# ProDoc_XIAOntegratedV2_2025-09-06.net
KiCad netlist of a schematic drawn in EasyEDA Pro
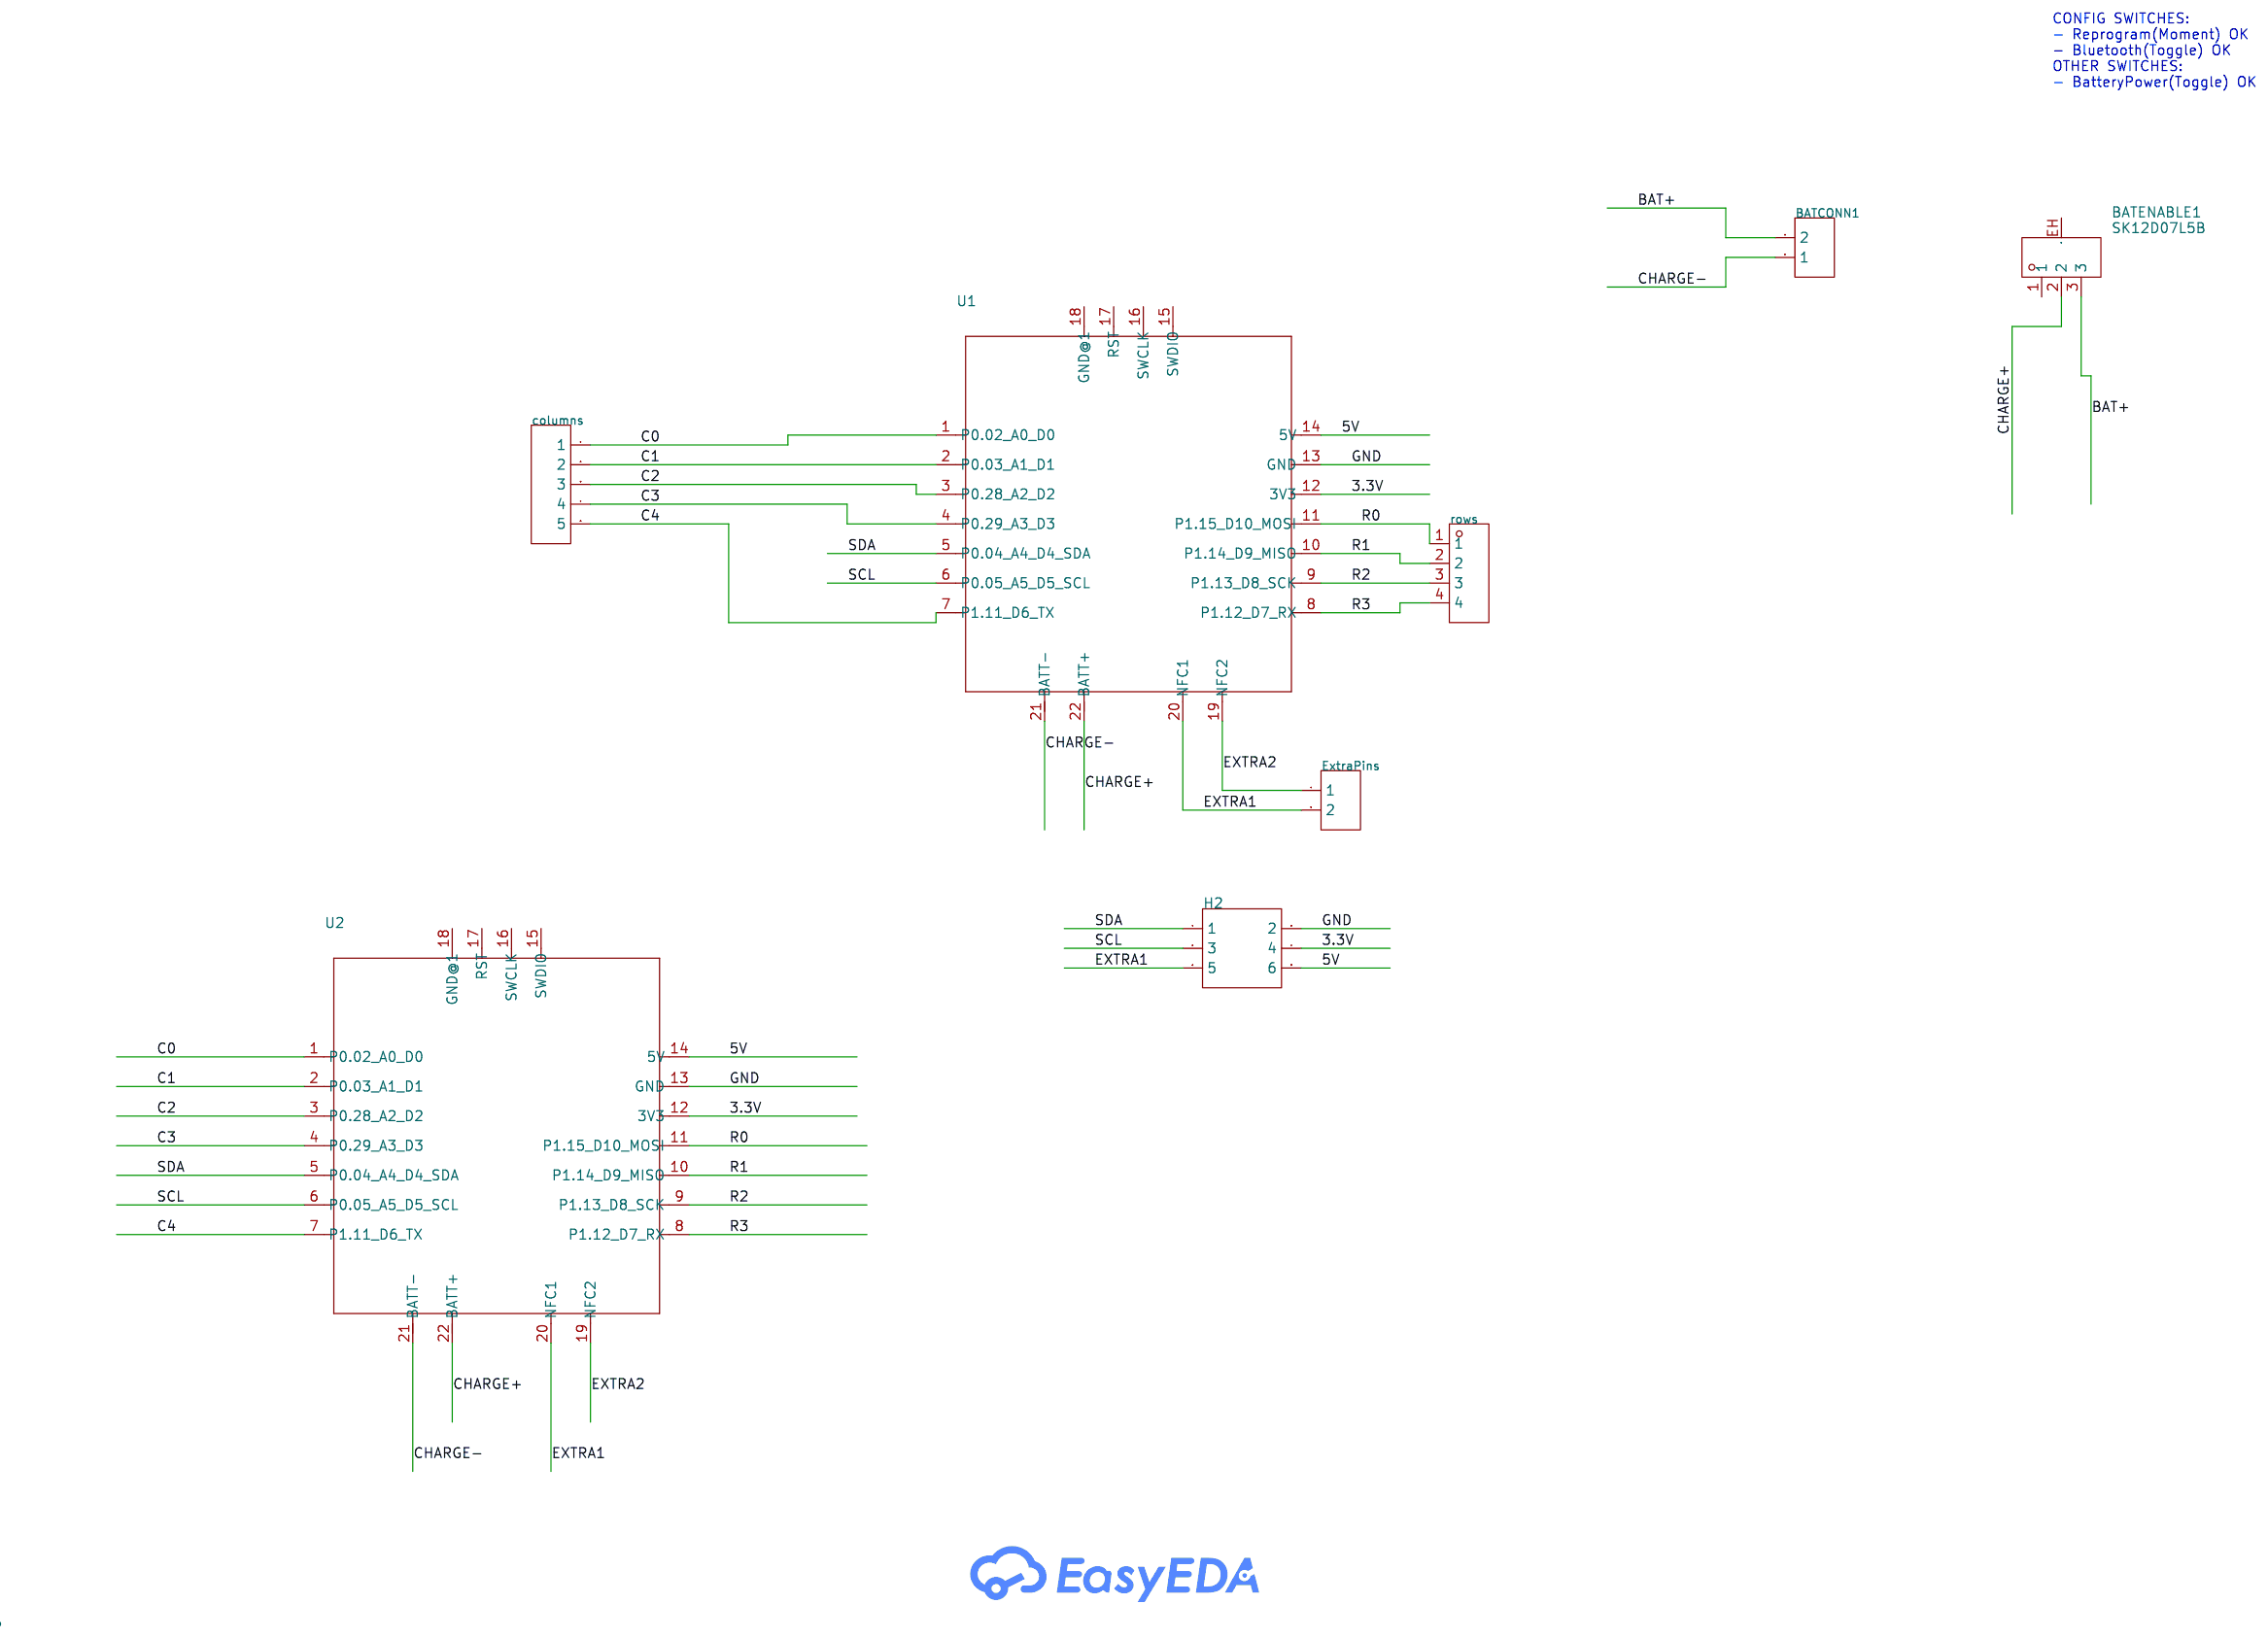
[diagram p0: schematic sheet]

(export (version "E")
  (design (tool "Eeschema 10.0.6"))
  (components
    (comp (ref "BATCONN1")
      (value "~")
      (footprint "easyedapro:HDR-TH_2P-P2.54-V-F")
      (libsource (lib "easyedapro") (part "Header-Female-2.54_1x2"))
    )
    (comp (ref "BATENABLE1")
      (value "SK12D07L5B")
      (footprint "easyedapro:SW-TH_SK-12D07-X-X")
      (fields (field (name "Manufacturer") "XKB Connection(中国星坤)"))
      (libsource (lib "easyedapro") (part "SK-12D07-L5-B"))
    )
    (comp (ref "columns")
      (value "~")
      (footprint "easyedapro:HDR-TH_5P-P2.54-V-F")
      (libsource (lib "easyedapro") (part "Header-Female-2.54_1x5"))
    )
    (comp (ref "ExtraPins")
      (value "~")
      (footprint "easyedapro:HDR-TH_2P-P2.54-V-F")
      (libsource (lib "easyedapro") (part "Header-Female-2.54_1x2"))
    )
    (comp (ref "H2")
      (value "~")
      (footprint "easyedapro:HDR-TH_6P-P2.54-V-F-R2-C3-S2.54")
      (libsource (lib "easyedapro") (part "HDR-F-2.54_2x3"))
    )
    (comp (ref "rows")
      (value "~")
      (footprint "easyedapro:HDR-TH_4P-P2.54-V-F")
      (libsource (lib "easyedapro") (part "2.54-1*4P母"))
    )
    (comp (ref "U1")
      (value "~")
      (footprint "easyedapro:XIAO-NRF52840/SENSE-MODULE14P-2.54-21X17.8MM")
      (libsource (lib "easyedapro") (part "XIAO-NRF52840/SENSE_"))
    )
    (comp (ref "U2")
      (value "~")
      (footprint "easyedapro:XIAO-NRF52840/SENSE-MODULE14P-2.54-21X17.8MM")
      (libsource (lib "easyedapro") (part "XIAO-NRF52840/SENSE_"))
    )
  )
  (nets
    (net (code "1") (name "/3.3V") (class "Default")
      (node (ref "H2") (pin "4") (pinfunction "4_4") (pintype "input"))
      (node (ref "U1") (pin "12") (pinfunction "3V3_12") (pintype "input"))
      (node (ref "U2") (pin "12") (pinfunction "3V3_12") (pintype "input"))
    )
    (net (code "2") (name "/5V") (class "Default")
      (node (ref "H2") (pin "6") (pinfunction "6_6") (pintype "input"))
      (node (ref "U1") (pin "14") (pinfunction "5V_14") (pintype "input"))
      (node (ref "U2") (pin "14") (pinfunction "5V_14") (pintype "input"))
    )
    (net (code "3") (name "/BAT+") (class "Default")
      (node (ref "BATCONN1") (pin "2") (pinfunction "2_2") (pintype "input"))
      (node (ref "BATENABLE1") (pin "3") (pinfunction "3_3") (pintype "unspecified"))
    )
    (net (code "4") (name "/C0") (class "Default")
      (node (ref "U1") (pin "1") (pinfunction "P0.02_A0_D0_1") (pintype "input"))
      (node (ref "U2") (pin "1") (pinfunction "P0.02_A0_D0_1") (pintype "input"))
      (node (ref "columns") (pin "1") (pinfunction "1_1") (pintype "input"))
    )
    (net (code "5") (name "/C1") (class "Default")
      (node (ref "U1") (pin "2") (pinfunction "P0.03_A1_D1_2") (pintype "input"))
      (node (ref "U2") (pin "2") (pinfunction "P0.03_A1_D1_2") (pintype "input"))
      (node (ref "columns") (pin "2") (pinfunction "2_2") (pintype "input"))
    )
    (net (code "6") (name "/C2") (class "Default")
      (node (ref "U1") (pin "3") (pinfunction "P0.28_A2_D2_3") (pintype "input"))
      (node (ref "U2") (pin "3") (pinfunction "P0.28_A2_D2_3") (pintype "input"))
      (node (ref "columns") (pin "3") (pinfunction "3_3") (pintype "input"))
    )
    (net (code "7") (name "/C3") (class "Default")
      (node (ref "U1") (pin "4") (pinfunction "P0.29_A3_D3_4") (pintype "input"))
      (node (ref "U2") (pin "4") (pinfunction "P0.29_A3_D3_4") (pintype "input"))
      (node (ref "columns") (pin "4") (pinfunction "4_4") (pintype "input"))
    )
    (net (code "8") (name "/C4") (class "Default")
      (node (ref "U1") (pin "7") (pinfunction "P1.11_D6_TX_7") (pintype "input"))
      (node (ref "U2") (pin "7") (pinfunction "P1.11_D6_TX_7") (pintype "input"))
      (node (ref "columns") (pin "5") (pinfunction "5_5") (pintype "input"))
    )
    (net (code "9") (name "/CHARGE+") (class "Default")
      (node (ref "BATENABLE1") (pin "2") (pinfunction "2_2") (pintype "unspecified"))
      (node (ref "U1") (pin "22") (pinfunction "BATT+_22") (pintype "input"))
      (node (ref "U2") (pin "22") (pinfunction "BATT+_22") (pintype "input"))
    )
    (net (code "10") (name "/CHARGE-") (class "Default")
      (node (ref "BATCONN1") (pin "1") (pinfunction "1_1") (pintype "input"))
      (node (ref "U1") (pin "21") (pinfunction "BATT-_21") (pintype "input"))
      (node (ref "U2") (pin "21") (pinfunction "BATT-_21") (pintype "input"))
    )
    (net (code "11") (name "/EXTRA1") (class "Default")
      (node (ref "ExtraPins") (pin "2") (pinfunction "2_2") (pintype "input"))
      (node (ref "H2") (pin "5") (pinfunction "5_5") (pintype "input"))
      (node (ref "U1") (pin "20") (pinfunction "NFC1_20") (pintype "input"))
      (node (ref "U2") (pin "20") (pinfunction "NFC1_20") (pintype "input"))
    )
    (net (code "12") (name "/EXTRA2") (class "Default")
      (node (ref "ExtraPins") (pin "1") (pinfunction "1_1") (pintype "input"))
      (node (ref "U1") (pin "19") (pinfunction "NFC2_19") (pintype "input"))
      (node (ref "U2") (pin "19") (pinfunction "NFC2_19") (pintype "input"))
    )
    (net (code "13") (name "/GND") (class "Default")
      (node (ref "H2") (pin "2") (pinfunction "2_2") (pintype "input"))
      (node (ref "U1") (pin "13") (pinfunction "GND_13") (pintype "input"))
      (node (ref "U2") (pin "13") (pinfunction "GND_13") (pintype "input"))
    )
    (net (code "14") (name "/R0") (class "Default")
      (node (ref "U1") (pin "11") (pinfunction "P1.15_D10_MOSI_11") (pintype "input"))
      (node (ref "U2") (pin "11") (pinfunction "P1.15_D10_MOSI_11") (pintype "input"))
      (node (ref "rows") (pin "1") (pinfunction "1_1") (pintype "input"))
    )
    (net (code "15") (name "/R1") (class "Default")
      (node (ref "U1") (pin "10") (pinfunction "P1.14_D9_MISO_10") (pintype "input"))
      (node (ref "U2") (pin "10") (pinfunction "P1.14_D9_MISO_10") (pintype "input"))
      (node (ref "rows") (pin "2") (pinfunction "2_2") (pintype "input"))
    )
    (net (code "16") (name "/R2") (class "Default")
      (node (ref "U1") (pin "9") (pinfunction "P1.13_D8_SCK_9") (pintype "input"))
      (node (ref "U2") (pin "9") (pinfunction "P1.13_D8_SCK_9") (pintype "input"))
      (node (ref "rows") (pin "3") (pinfunction "3_3") (pintype "input"))
    )
    (net (code "17") (name "/R3") (class "Default")
      (node (ref "U1") (pin "8") (pinfunction "P1.12_D7_RX_8") (pintype "input"))
      (node (ref "U2") (pin "8") (pinfunction "P1.12_D7_RX_8") (pintype "input"))
      (node (ref "rows") (pin "4") (pinfunction "4_4") (pintype "input"))
    )
    (net (code "18") (name "/SCL") (class "Default")
      (node (ref "H2") (pin "3") (pinfunction "3_3") (pintype "input"))
      (node (ref "U1") (pin "6") (pinfunction "P0.05_A5_D5_SCL_6") (pintype "input"))
      (node (ref "U2") (pin "6") (pinfunction "P0.05_A5_D5_SCL_6") (pintype "input"))
    )
    (net (code "19") (name "/SDA") (class "Default")
      (node (ref "H2") (pin "1") (pinfunction "1_1") (pintype "input"))
      (node (ref "U1") (pin "5") (pinfunction "P0.04_A4_D4_SDA_5") (pintype "input"))
      (node (ref "U2") (pin "5") (pinfunction "P0.04_A4_D4_SDA_5") (pintype "input"))
    )
    (net (code "20") (name "unconnected-(BATENABLE1-Pad1)") (class "Default")
      (node (ref "BATENABLE1") (pin "1") (pinfunction "1_1") (pintype "unspecified"))
    )
    (net (code "21") (name "unconnected-(BATENABLE1-PadEH)") (class "Default")
      (node (ref "BATENABLE1") (pin "EH") (pinfunction "EH_EH") (pintype "unspecified"))
    )
    (net (code "22") (name "unconnected-(U1-GND@1-Pad18)") (class "Default")
      (node (ref "U1") (pin "18") (pinfunction "GND@1_18") (pintype "input"))
    )
    (net (code "23") (name "unconnected-(U1-RST-Pad17)") (class "Default")
      (node (ref "U1") (pin "17") (pinfunction "RST_17") (pintype "input"))
    )
    (net (code "24") (name "unconnected-(U1-SWCLK-Pad16)") (class "Default")
      (node (ref "U1") (pin "16") (pinfunction "SWCLK_16") (pintype "input"))
    )
    (net (code "25") (name "unconnected-(U1-SWDIO-Pad15)") (class "Default")
      (node (ref "U1") (pin "15") (pinfunction "SWDIO_15") (pintype "input"))
    )
    (net (code "26") (name "unconnected-(U2-GND@1-Pad18)") (class "Default")
      (node (ref "U2") (pin "18") (pinfunction "GND@1_18") (pintype "input"))
    )
    (net (code "27") (name "unconnected-(U2-RST-Pad17)") (class "Default")
      (node (ref "U2") (pin "17") (pinfunction "RST_17") (pintype "input"))
    )
    (net (code "28") (name "unconnected-(U2-SWCLK-Pad16)") (class "Default")
      (node (ref "U2") (pin "16") (pinfunction "SWCLK_16") (pintype "input"))
    )
    (net (code "29") (name "unconnected-(U2-SWDIO-Pad15)") (class "Default")
      (node (ref "U2") (pin "15") (pinfunction "SWDIO_15") (pintype "input"))
    )
  )
)
